# REG_3_3V.net
KiCad netlist of a schematic drawn in Altium Designer
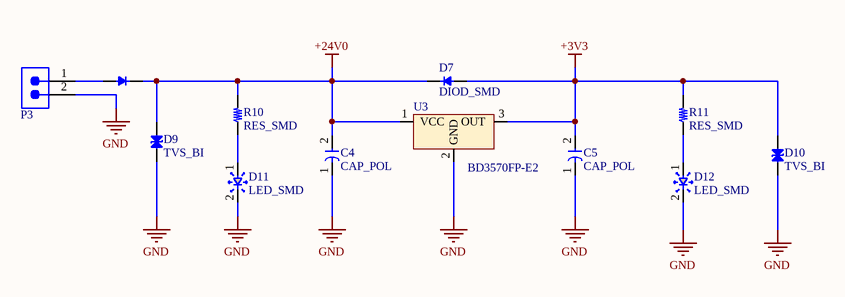
[diagram p0: REG_3.3V.SchDoc]

(export (version "E")
  (design (tool "Eeschema 10.0.6"))
  (components
    (comp (ref "C4")
      (value "CAP_POL")
      (footprint "CAP_SMC")
      (libsource (lib "radmehr_library") (part "CAP_POL"))
    )
    (comp (ref "C5")
      (value "CAP_POL")
      (footprint "CAP_SMA")
      (libsource (lib "radmehr_library") (part "CAP_POL"))
    )
    (comp (ref "D7")
      (value "DIOD_SMD")
      (footprint "DIOD_SMA")
      (libsource (lib "radmehr_library") (part "DIOD_SMD"))
    )
    (comp (ref "D8")
      (value "DIOD_SMD")
      (footprint "DIOD_SMA")
      (libsource (lib "radmehr_library") (part "DIOD_SMD"))
    )
    (comp (ref "D9")
      (value "TVS_BI")
      (footprint "DIOD_SMB")
      (libsource (lib "radmehr_library") (part "DIOD_SMD_TVS_BI"))
    )
    (comp (ref "D10")
      (value "TVS_BI")
      (footprint "DIOD_SMB")
      (libsource (lib "radmehr_library") (part "DIOD_SMD_TVS_BI"))
    )
    (comp (ref "D11")
      (value "LED_SMD")
      (footprint "D 0603")
      (libsource (lib "radmehr_library") (part "LED_SMD"))
    )
    (comp (ref "D12")
      (value "LED_SMD")
      (footprint "D 0603")
      (libsource (lib "radmehr_library") (part "LED_SMD"))
    )
    (comp (ref "P3")
      (value "691321300002")
      (footprint "691321300002")
      (description "WR-TBL Series 321 Vertical PCB Header, Through Hole, pitch 3.81mm, 2p")
      (fields (field (name "MANUFACTURER") "Wurth Elektronik"))
      (libsource (lib "Altium_WR-TBL (rev22a)") (part "691321300002"))
    )
    (comp (ref "R10")
      (value "RES_SMD")
      (footprint "R 0603")
      (libsource (lib "radmehr_library") (part "RES_SMD"))
    )
    (comp (ref "R11")
      (value "RES_SMD")
      (footprint "R 0603")
      (libsource (lib "radmehr_library") (part "RES_SMD"))
    )
    (comp (ref "U3")
      (value "BD3570FP-E2")
      (footprint "DPAK-U")
      (libsource (lib "radmehr_library") (part "BD3570FP-E2"))
    )
  )
  (nets
    (net (code "1") (name "+3V3") (class "Default")
      (node (ref "C5") (pin "2") (pinfunction "2_2") (pintype "passive"))
      (node (ref "D10") (pin "2") (pinfunction "2_2") (pintype "passive"))
      (node (ref "D7") (pin "1") (pinfunction "1_1") (pintype "passive"))
      (node (ref "R11") (pin "2") (pinfunction "2_2") (pintype "passive"))
      (node (ref "U3") (pin "3") (pinfunction "OUT_3") (pintype "power_in"))
    )
    (net (code "2") (name "+24V0") (class "Default")
      (node (ref "C4") (pin "2") (pinfunction "2_2") (pintype "passive"))
      (node (ref "D7") (pin "2") (pinfunction "2_2") (pintype "passive"))
      (node (ref "D8") (pin "2") (pinfunction "2_2") (pintype "passive"))
      (node (ref "D9") (pin "2") (pinfunction "2_2") (pintype "passive"))
      (node (ref "R10") (pin "2") (pinfunction "2_2") (pintype "passive"))
      (node (ref "U3") (pin "1") (pinfunction "VCC_1") (pintype "power_in"))
    )
    (net (code "3") (name "GND") (class "Default")
      (node (ref "C4") (pin "1") (pinfunction "1_1") (pintype "passive"))
      (node (ref "C5") (pin "1") (pinfunction "1_1") (pintype "passive"))
      (node (ref "D10") (pin "1") (pinfunction "1_1") (pintype "passive"))
      (node (ref "D11") (pin "2") (pintype "passive"))
      (node (ref "D12") (pin "2") (pintype "passive"))
      (node (ref "D9") (pin "1") (pinfunction "1_1") (pintype "passive"))
      (node (ref "P3") (pin "2") (pinfunction "2_2") (pintype "passive"))
      (node (ref "U3") (pin "2") (pinfunction "GND_2") (pintype "power_in"))
    )
    (net (code "4") (name "Net-(D8-Pad1)") (class "Default")
      (node (ref "D8") (pin "1") (pinfunction "1_1") (pintype "passive"))
      (node (ref "P3") (pin "1") (pinfunction "1_1") (pintype "passive"))
    )
    (net (code "5") (name "Net-(D11-Pad1)") (class "Default")
      (node (ref "D11") (pin "1") (pintype "passive"))
      (node (ref "R10") (pin "1") (pinfunction "1_1") (pintype "passive"))
    )
    (net (code "6") (name "Net-(D12-Pad1)") (class "Default")
      (node (ref "D12") (pin "1") (pintype "passive"))
      (node (ref "R11") (pin "1") (pinfunction "1_1") (pintype "passive"))
    )
  )
)
